# ControlBoard.net
KiCad netlist of a schematic drawn in Altium Designer
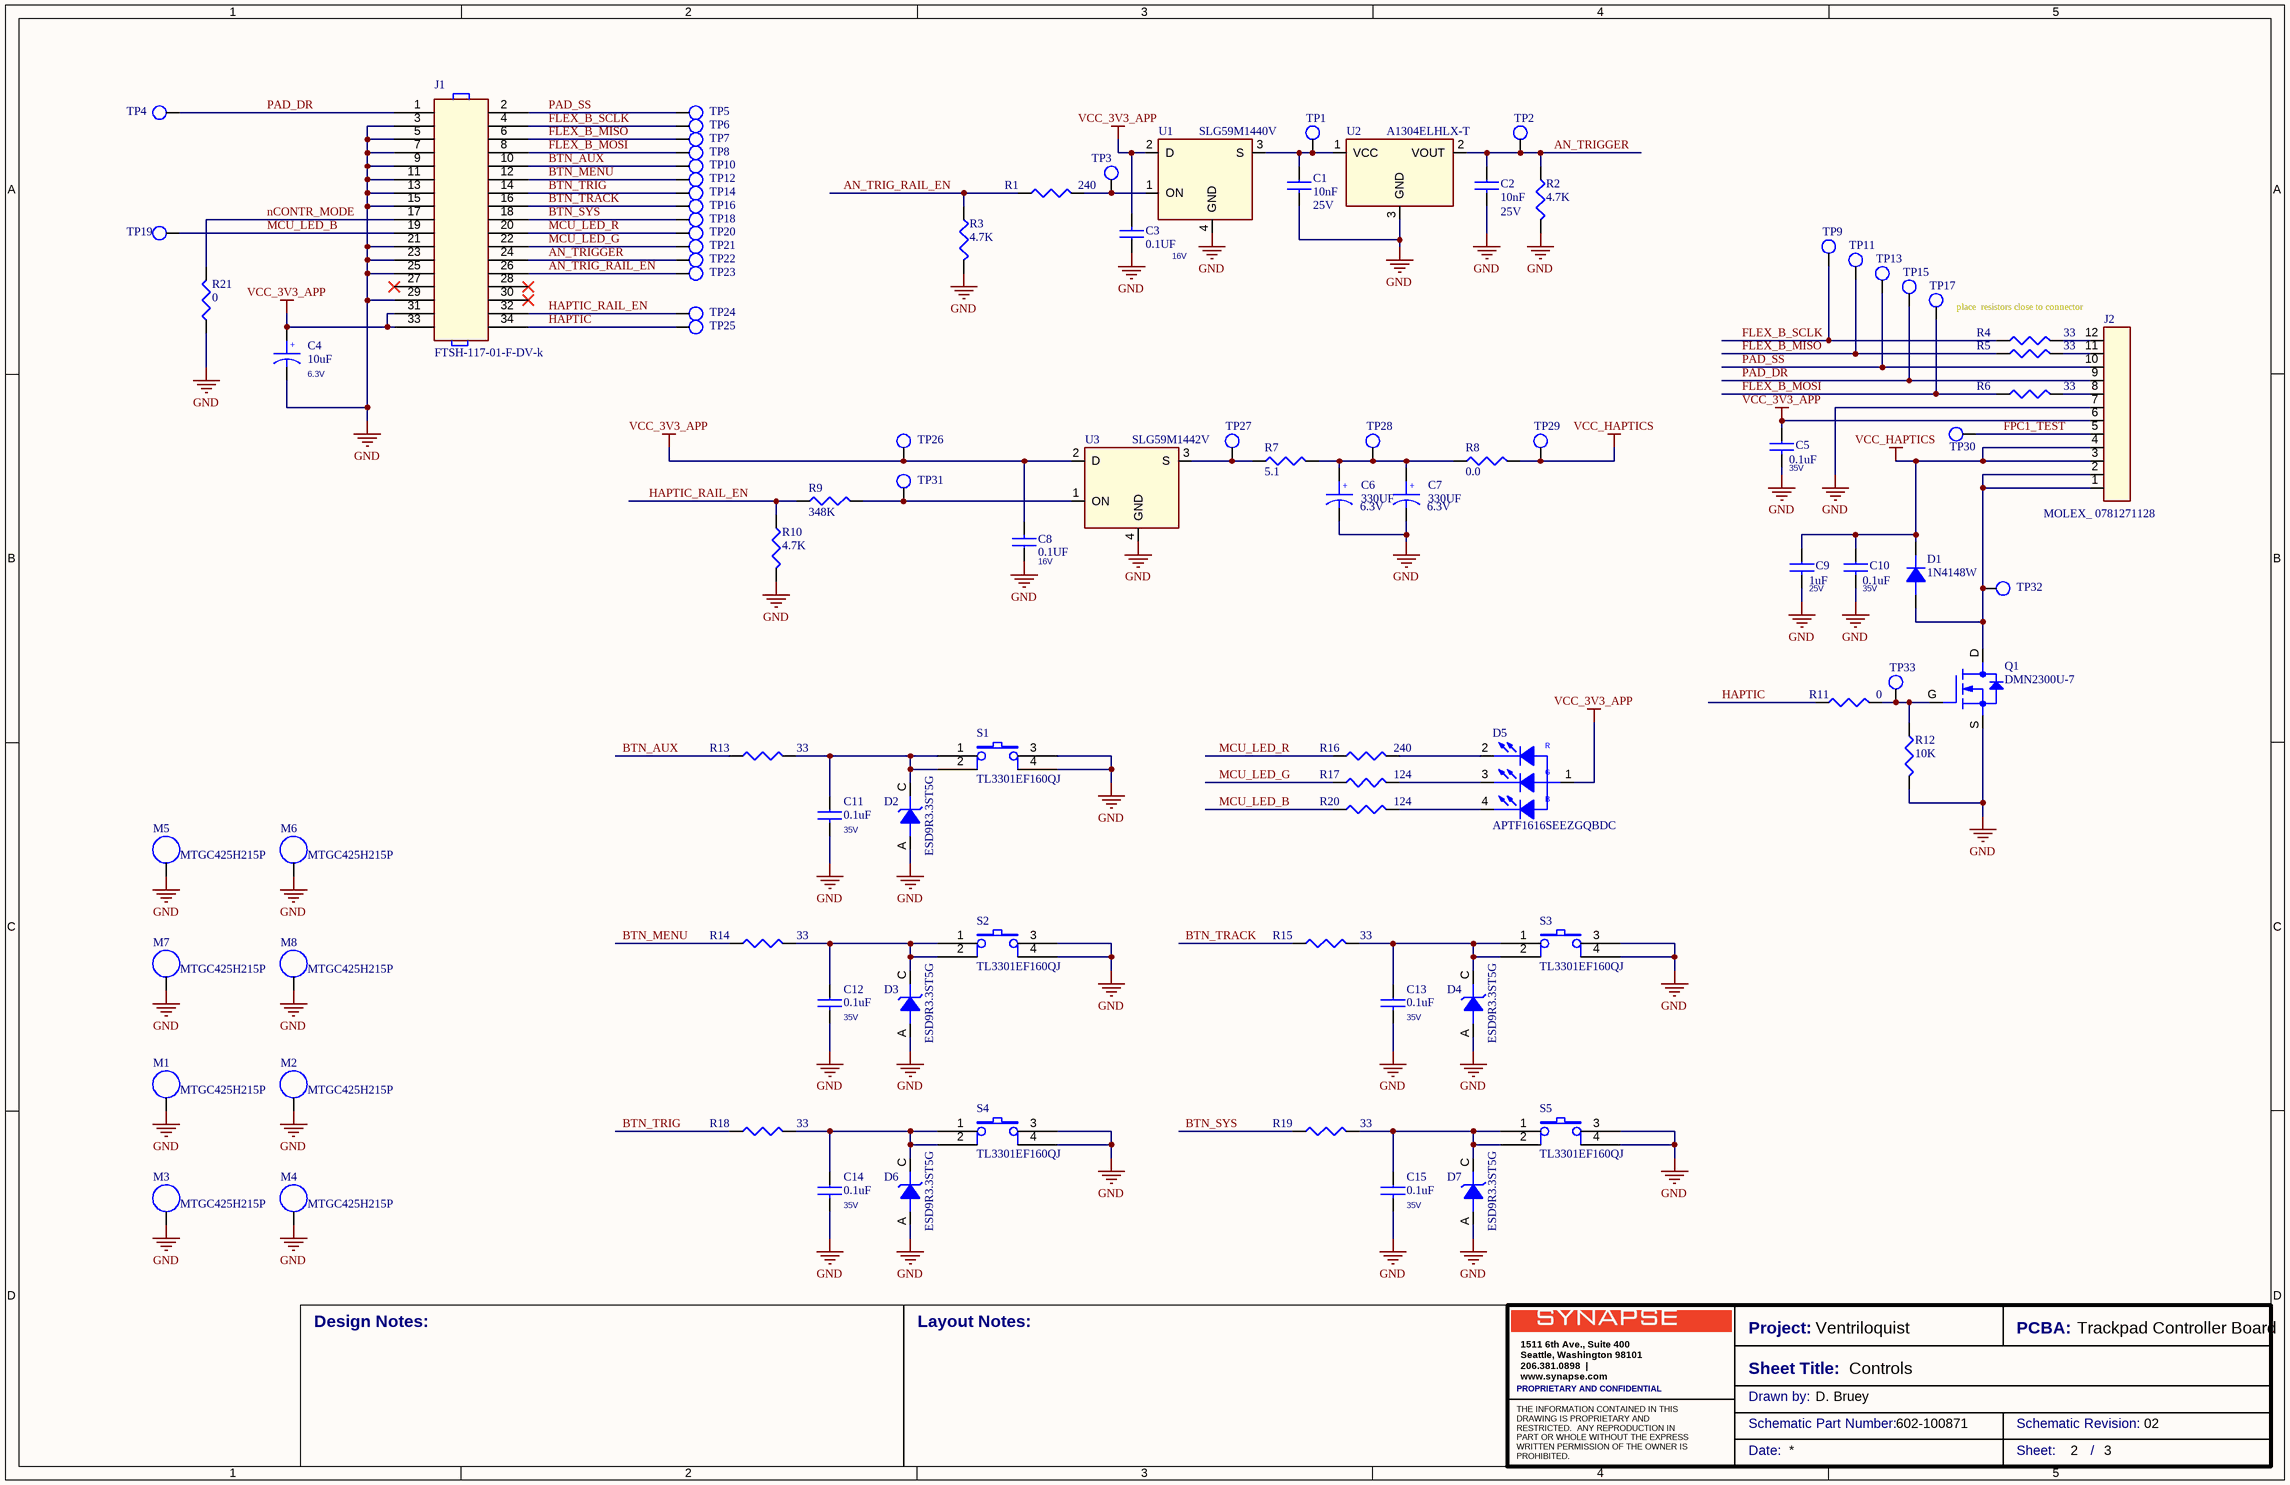
[diagram p0: ControlBoard.SchDoc]

(export (version "E")
  (design (tool "Eeschema 10.0.6"))
  (components
    (comp (ref "C1")
      (value "10nF")
      (footprint "0402-ipcsm_60")
      (description "CAP CER 10000PF 25V 10% X7R 0402")
      (fields (field (name "VOLTAGE") "25V") (field (name "MFG") "TDK") (field (name "TOLERANCE") "10%"))
      (libsource (lib "SynapseLibrary") (part "CAP"))
    )
    (comp (ref "C2")
      (value "10nF")
      (footprint "0402-ipcsm_60")
      (description "CAP CER 10000PF 25V 10% X7R 0402")
      (fields (field (name "VOLTAGE") "25V") (field (name "MFG") "TDK") (field (name "TOLERANCE") "10%"))
      (libsource (lib "SynapseLibrary") (part "CAP"))
    )
    (comp (ref "C3")
      (value "0.1UF")
      (footprint "0603-ipcsm_90")
      (description "CAP CER 0.1UF 16V 5% X7R 0603")
      (fields (field (name "VOLTAGE") "16V") (field (name "MFG") "Kemet") (field (name "TOLERANCE") "5%"))
      (libsource (lib "SynapseLibrary") (part "CAP"))
    )
    (comp (ref "C4")
      (value "10uF")
      (footprint "c-0603-POL_35H")
      (description "CAP TANT 10UF 6.3V 20% 0603")
      (fields
        (field (name "VOLTAGE") "6.3V")
        (field (name "MFG") "Vishay/Sprague")
        (field (name "TOLERANCE") "20%")
      )
      (libsource (lib "SynapseLibrary") (part "CAP_POL"))
    )
    (comp (ref "C5")
      (value "0.1uF")
      (footprint "0402-IPCsm_55")
      (description "CAP CER 0.1UF 35V 10% X5R 0402")
      (fields
        (field (name "VOLTAGE") "35V")
        (field (name "MFG") "TAIYO YUDEN")
        (field (name "TOLERANCE") "±10%")
      )
      (libsource (lib "SynapseLibrary") (part "CAP"))
    )
    (comp (ref "C6")
      (value "330UF")
      (footprint "c-elect_FK-D8")
      (description "CAP ALUM 330UF 20% 6.3V SMD")
      (fields
        (field (name "VOLTAGE") "6.3V")
        (field (name "MFG") "PANASONIC")
        (field (name "TOLERANCE") "20%")
      )
      (libsource (lib "SynapseLibrary") (part "CAP_POL"))
    )
    (comp (ref "C7")
      (value "330UF")
      (footprint "c-elect_FK-D8")
      (description "CAP ALUM 330UF 20% 6.3V SMD")
      (fields
        (field (name "VOLTAGE") "6.3V")
        (field (name "MFG") "PANASONIC")
        (field (name "TOLERANCE") "20%")
      )
      (libsource (lib "SynapseLibrary") (part "CAP_POL"))
    )
    (comp (ref "C8")
      (value "0.1UF")
      (footprint "0603-ipcsm_90")
      (description "CAP CER 0.1UF 16V 5% X7R 0603")
      (fields (field (name "VOLTAGE") "16V") (field (name "MFG") "Kemet") (field (name "TOLERANCE") "5%"))
      (libsource (lib "SynapseLibrary") (part "CAP"))
    )
    (comp (ref "C9")
      (value "1uF")
      (footprint "0603-IPCsm_90")
      (description "CAP CER 1UF 25V 10% X5R 0603")
      (fields (field (name "VOLTAGE") "25V") (field (name "MFG") "Murata") (field (name "TOLERANCE") "10%"))
      (libsource (lib "SynapseLibrary") (part "CAP"))
    )
    (comp (ref "C10")
      (value "0.1uF")
      (footprint "0402-IPCsm_55")
      (description "CAP CER 0.1UF 35V 10% X5R 0402")
      (fields
        (field (name "VOLTAGE") "35V")
        (field (name "MFG") "TAIYO YUDEN")
        (field (name "TOLERANCE") "±10%")
      )
      (libsource (lib "SynapseLibrary") (part "CAP"))
    )
    (comp (ref "C11")
      (value "0.1uF")
      (footprint "0402-IPCsm_55")
      (description "CAP CER 0.1UF 35V 10% X5R 0402")
      (fields
        (field (name "VOLTAGE") "35V")
        (field (name "MFG") "TAIYO YUDEN")
        (field (name "TOLERANCE") "±10%")
      )
      (libsource (lib "SynapseLibrary") (part "CAP"))
    )
    (comp (ref "C12")
      (value "0.1uF")
      (footprint "0402-IPCsm_55")
      (description "CAP CER 0.1UF 35V 10% X5R 0402")
      (fields
        (field (name "VOLTAGE") "35V")
        (field (name "MFG") "TAIYO YUDEN")
        (field (name "TOLERANCE") "±10%")
      )
      (libsource (lib "SynapseLibrary") (part "CAP"))
    )
    (comp (ref "C13")
      (value "0.1uF")
      (footprint "0402-IPCsm_55")
      (description "CAP CER 0.1UF 35V 10% X5R 0402")
      (fields
        (field (name "VOLTAGE") "35V")
        (field (name "MFG") "TAIYO YUDEN")
        (field (name "TOLERANCE") "±10%")
      )
      (libsource (lib "SynapseLibrary") (part "CAP"))
    )
    (comp (ref "C14")
      (value "0.1uF")
      (footprint "0402-IPCsm_55")
      (description "CAP CER 0.1UF 35V 10% X5R 0402")
      (fields
        (field (name "VOLTAGE") "35V")
        (field (name "MFG") "TAIYO YUDEN")
        (field (name "TOLERANCE") "±10%")
      )
      (libsource (lib "SynapseLibrary") (part "CAP"))
    )
    (comp (ref "C15")
      (value "0.1uF")
      (footprint "0402-IPCsm_55")
      (description "CAP CER 0.1UF 35V 10% X5R 0402")
      (fields
        (field (name "VOLTAGE") "35V")
        (field (name "MFG") "TAIYO YUDEN")
        (field (name "TOLERANCE") "±10%")
      )
      (libsource (lib "SynapseLibrary") (part "CAP"))
    )
    (comp (ref "D1")
      (value "1N4148W")
      (footprint "SOD123_135")
      (description "DIODE SWITCH 100V 0.15A SOD123")
      (fields (field (name "MFG") "Micro Commercial Co") (field (name "VOLTAGE") "100V"))
      (libsource (lib "SynapseLibrary") (part "DIODE"))
    )
    (comp (ref "D2")
      (value "ESD9R3.3ST5G")
      (footprint "sod923-40")
      (description "TVS DIODE 3.3VWM 7.8VC SOD923")
      (fields (field (name "MFG") "On Semiconductor") (field (name "VOLTAGE") "3.3V"))
      (libsource (lib "SynapseLibrary") (part "TVS_UNI"))
    )
    (comp (ref "D3")
      (value "ESD9R3.3ST5G")
      (footprint "sod923-40")
      (description "TVS DIODE 3.3VWM 7.8VC SOD923")
      (fields (field (name "MFG") "On Semiconductor") (field (name "VOLTAGE") "3.3V"))
      (libsource (lib "SynapseLibrary") (part "TVS_UNI"))
    )
    (comp (ref "D4")
      (value "ESD9R3.3ST5G")
      (footprint "sod923-40")
      (description "TVS DIODE 3.3VWM 7.8VC SOD923")
      (fields (field (name "MFG") "On Semiconductor") (field (name "VOLTAGE") "3.3V"))
      (libsource (lib "SynapseLibrary") (part "TVS_UNI"))
    )
    (comp (ref "D5")
      (value "APTF1616SEEZGQBDC")
      (footprint "led_RBG_1p6x1p6_sm")
      (description "LED RGB CLEAR 0606 SMD")
      (fields (field (name "MFG") "Kingbright"))
      (libsource (lib "SynapseLibrary") (part "RGB_CA_HT-B3053FCH"))
    )
    (comp (ref "D6")
      (value "ESD9R3.3ST5G")
      (footprint "sod923-40")
      (description "TVS DIODE 3.3VWM 7.8VC SOD923")
      (fields (field (name "MFG") "On Semiconductor") (field (name "VOLTAGE") "3.3V"))
      (libsource (lib "SynapseLibrary") (part "TVS_UNI"))
    )
    (comp (ref "D7")
      (value "ESD9R3.3ST5G")
      (footprint "sod923-40")
      (description "TVS DIODE 3.3VWM 7.8VC SOD923")
      (fields (field (name "MFG") "On Semiconductor") (field (name "VOLTAGE") "3.3V"))
      (libsource (lib "SynapseLibrary") (part "TVS_UNI"))
    )
    (comp (ref "J1")
      (value "FTSH-117-01-F-DV-k")
      (footprint "FTSH-117-01-XXX-DV-K")
      (description "34 Positions Header, Shrouded Connector 0.050\" (1.27mm) Surface Mount Gold")
      (fields (field (name "MFG") "Samtec"))
      (libsource (lib "SynapseLibrary") (part "HEADER 17X2"))
    )
    (comp (ref "J2")
      (value "MOLEX_ 0781271128")
      (footprint "con12_molex_0781271128")
      (description "CONN FFC VERT 12POS 0.50MM SMD")
      (fields (field (name "MFG") "MOLEX"))
      (libsource (lib "SynapseLibrary") (part "HEADER12"))
    )
    (comp (ref "M1")
      (value "MTGC425H215P")
      (footprint "MTGC425H215P")
      (description "MTG, 4.25mm PAD, 2.15mm Plated Hole")
      (libsource (lib "SynapseLibrary") (part "MTG"))
    )
    (comp (ref "M2")
      (value "MTGC425H215P")
      (footprint "MTGC425H215P")
      (description "MTG, 4.25mm PAD, 2.15mm Plated Hole")
      (libsource (lib "SynapseLibrary") (part "MTG"))
    )
    (comp (ref "M3")
      (value "MTGC425H215P")
      (footprint "MTGC425H215P")
      (description "MTG, 4.25mm PAD, 2.15mm Plated Hole")
      (libsource (lib "SynapseLibrary") (part "MTG"))
    )
    (comp (ref "M4")
      (value "MTGC425H215P")
      (footprint "MTGC425H215P")
      (description "MTG, 4.25mm PAD, 2.15mm Plated Hole")
      (libsource (lib "SynapseLibrary") (part "MTG"))
    )
    (comp (ref "M5")
      (value "MTGC425H215P")
      (footprint "MTGC425H215P")
      (description "MTG, 4.25mm PAD, 2.15mm Plated Hole")
      (libsource (lib "SynapseLibrary") (part "MTG"))
    )
    (comp (ref "M6")
      (value "MTGC425H215P")
      (footprint "MTGC425H215P")
      (description "MTG, 4.25mm PAD, 2.15mm Plated Hole")
      (libsource (lib "SynapseLibrary") (part "MTG"))
    )
    (comp (ref "M7")
      (value "MTGC425H215P")
      (footprint "MTGC425H215P")
      (description "MTG, 4.25mm PAD, 2.15mm Plated Hole")
      (libsource (lib "SynapseLibrary") (part "MTG"))
    )
    (comp (ref "M8")
      (value "MTGC425H215P")
      (footprint "MTGC425H215P")
      (description "MTG, 4.25mm PAD, 2.15mm Plated Hole")
      (libsource (lib "SynapseLibrary") (part "MTG"))
    )
    (comp (ref "Q1")
      (value "DMN2300U-7")
      (footprint "SOT23-GSD_47H_DMN2075U")
      (description "MOSFET N-CH 20V 1.24A SOT23")
      (fields (field (name "MFG") "Diodes") (field (name "VOLTAGE") "20V"))
      (libsource (lib "SynapseLibrary") (part "MOSFET_N_EN_3PIN"))
    )
    (comp (ref "R1")
      (value "240")
      (footprint "0402-IPCsm_40")
      (description "RES 240 OHM 1/10W 1% 0402 SMD")
      (fields (field (name "TOLERANCE") "1%") (field (name "MFG") "Panasonic"))
      (libsource (lib "SynapseLibrary") (part "RES"))
    )
    (comp (ref "R2")
      (value "4.7K")
      (footprint "0402-IPCsm_40")
      (description "RES 4.70K OHM 1/10W 1% 0402 SMD")
      (fields (field (name "TOLERANCE") "1.00%") (field (name "VOLTAGE") "50V"))
      (libsource (lib "SynapseLibrary") (part "RES"))
    )
    (comp (ref "R3")
      (value "4.7K")
      (footprint "0402-IPCsm_40")
      (description "RES 4.70K OHM 1/10W 1% 0402 SMD")
      (fields (field (name "TOLERANCE") "1.00%") (field (name "VOLTAGE") "50V"))
      (libsource (lib "SynapseLibrary") (part "RES"))
    )
    (comp (ref "R4")
      (value "33")
      (footprint "0402-IPCsm_40")
      (description "RES 33 OHM 1/16W 5% 0402 SMD")
      (fields (field (name "TOLERANCE") "5.00%") (field (name "VOLTAGE") "50V"))
      (libsource (lib "SynapseLibrary") (part "RES"))
    )
    (comp (ref "R5")
      (value "33")
      (footprint "0402-IPCsm_40")
      (description "RES 33 OHM 1/16W 5% 0402 SMD")
      (fields (field (name "TOLERANCE") "5.00%") (field (name "VOLTAGE") "50V"))
      (libsource (lib "SynapseLibrary") (part "RES"))
    )
    (comp (ref "R6")
      (value "33")
      (footprint "0402-IPCsm_40")
      (description "RES 33 OHM 1/16W 5% 0402 SMD")
      (fields (field (name "TOLERANCE") "5.00%") (field (name "VOLTAGE") "50V"))
      (libsource (lib "SynapseLibrary") (part "RES"))
    )
    (comp (ref "R7")
      (value "5.1")
      (footprint "r-1206_28H")
      (description "RES SMD 5.1 OHM 5% 1/4W 1206")
      (fields (field (name "TOLERANCE") "5.00%") (field (name "MFG") "Yageo"))
      (libsource (lib "SynapseLibrary") (part "RES"))
    )
    (comp (ref "R8")
      (value "0.0")
      (footprint "r-1206_28H")
      (description "RES ZERO OHM 1/4W 5% 1206 SMD")
      (fields (field (name "TOLERANCE") "5.00%") (field (name "VOLTAGE") "200V"))
      (libsource (lib "SynapseLibrary") (part "RES"))
    )
    (comp (ref "R9")
      (value "348K")
      (footprint "0402-IPCsm_40")
      (description "RES SMD 348K OHM 1% 1/10W 0402")
      (fields (field (name "TOLERANCE") "1.00%") (field (name "MFG") "PANASONIC"))
      (libsource (lib "SynapseLibrary") (part "RES"))
    )
    (comp (ref "R10")
      (value "4.7K")
      (footprint "0402-IPCsm_40")
      (description "RES 4.70K OHM 1/10W 1% 0402 SMD")
      (fields (field (name "TOLERANCE") "1.00%") (field (name "VOLTAGE") "50V"))
      (libsource (lib "SynapseLibrary") (part "RES"))
    )
    (comp (ref "R11")
      (value "0")
      (footprint "0402-IPCsm_40")
      (description "RES 0.0 OHM 1/10W JUMP 0402 SMD")
      (fields (field (name "TOLERANCE") "5.00%") (field (name "MFG") "PANASONIC"))
      (libsource (lib "SynapseLibrary") (part "RES"))
    )
    (comp (ref "R12")
      (value "10K")
      (footprint "0402-IPCsm_40")
      (description "RES 10K OHM 1/10W 5% 0402 SMD")
      (fields (field (name "TOLERANCE") "5%") (field (name "MFG") "Panasonic"))
      (libsource (lib "SynapseLibrary") (part "RES"))
    )
    (comp (ref "R13")
      (value "33")
      (footprint "0402-IPCsm_40")
      (description "RES 33 OHM 1/16W 5% 0402 SMD")
      (fields (field (name "TOLERANCE") "5.00%") (field (name "VOLTAGE") "50V"))
      (libsource (lib "SynapseLibrary") (part "RES"))
    )
    (comp (ref "R14")
      (value "33")
      (footprint "0402-IPCsm_40")
      (description "RES 33 OHM 1/16W 5% 0402 SMD")
      (fields (field (name "TOLERANCE") "5.00%") (field (name "VOLTAGE") "50V"))
      (libsource (lib "SynapseLibrary") (part "RES"))
    )
    (comp (ref "R15")
      (value "33")
      (footprint "0402-IPCsm_40")
      (description "RES 33 OHM 1/16W 5% 0402 SMD")
      (fields (field (name "TOLERANCE") "5.00%") (field (name "VOLTAGE") "50V"))
      (libsource (lib "SynapseLibrary") (part "RES"))
    )
    (comp (ref "R16")
      (value "240")
      (footprint "0402-IPCsm_40")
      (description "RES 240 OHM 1/10W 1% 0402 SMD")
      (fields (field (name "TOLERANCE") "1%") (field (name "MFG") "Panasonic"))
      (libsource (lib "SynapseLibrary") (part "RES"))
    )
    (comp (ref "R17")
      (value "124")
      (footprint "0402-IPCsm_40")
      (description "RES SMD 124 OHM 1% 1/16W 0402")
      (fields (field (name "TOLERANCE") "1.00%") (field (name "MFG") "Yageo"))
      (libsource (lib "SynapseLibrary") (part "RES"))
    )
    (comp (ref "R18")
      (value "33")
      (footprint "0402-IPCsm_40")
      (description "RES 33 OHM 1/16W 5% 0402 SMD")
      (fields (field (name "TOLERANCE") "5.00%") (field (name "VOLTAGE") "50V"))
      (libsource (lib "SynapseLibrary") (part "RES"))
    )
    (comp (ref "R19")
      (value "33")
      (footprint "0402-IPCsm_40")
      (description "RES 33 OHM 1/16W 5% 0402 SMD")
      (fields (field (name "TOLERANCE") "5.00%") (field (name "VOLTAGE") "50V"))
      (libsource (lib "SynapseLibrary") (part "RES"))
    )
    (comp (ref "R20")
      (value "124")
      (footprint "0402-IPCsm_40")
      (description "RES SMD 124 OHM 1% 1/16W 0402")
      (fields (field (name "TOLERANCE") "1.00%") (field (name "MFG") "Yageo"))
      (libsource (lib "SynapseLibrary") (part "RES"))
    )
    (comp (ref "R21")
      (value "0")
      (footprint "0402-IPCsm_40")
      (description "RES 0.0 OHM 1/10W JUMP 0402 SMD")
      (fields (field (name "TOLERANCE") "5.00%") (field (name "MFG") "PANASONIC"))
      (libsource (lib "SynapseLibrary") (part "RES"))
    )
    (comp (ref "S1")
      (value "TL3301EF160QJ")
      (footprint "SW_TL3301_J")
      (description "SWITCH TACTILE SPST-NO 0.05A 12V")
      (fields (field (name "PART NUMBER") "TL3301AF260QG") (field (name "MANUFACTURER") "E-Switch"))
      (libsource (lib "SynapseLibrary") (part "ESWITCH_TL3301AF"))
    )
    (comp (ref "S2")
      (value "TL3301EF160QJ")
      (footprint "SW_TL3301_J")
      (description "SWITCH TACTILE SPST-NO 0.05A 12V")
      (fields (field (name "PART NUMBER") "TL3301AF260QG") (field (name "MANUFACTURER") "E-Switch"))
      (libsource (lib "SynapseLibrary") (part "ESWITCH_TL3301AF"))
    )
    (comp (ref "S3")
      (value "TL3301EF160QJ")
      (footprint "SW_TL3301_J")
      (description "SWITCH TACTILE SPST-NO 0.05A 12V")
      (fields (field (name "PART NUMBER") "TL3301AF260QG") (field (name "MANUFACTURER") "E-Switch"))
      (libsource (lib "SynapseLibrary") (part "ESWITCH_TL3301AF"))
    )
    (comp (ref "S4")
      (value "TL3301EF160QJ")
      (footprint "SW_TL3301_J")
      (description "SWITCH TACTILE SPST-NO 0.05A 12V")
      (fields (field (name "PART NUMBER") "TL3301AF260QG") (field (name "MANUFACTURER") "E-Switch"))
      (libsource (lib "SynapseLibrary") (part "ESWITCH_TL3301AF"))
    )
    (comp (ref "S5")
      (value "TL3301EF160QJ")
      (footprint "SW_TL3301_J")
      (description "SWITCH TACTILE SPST-NO 0.05A 12V")
      (fields (field (name "PART NUMBER") "TL3301AF260QG") (field (name "MANUFACTURER") "E-Switch"))
      (libsource (lib "SynapseLibrary") (part "ESWITCH_TL3301AF"))
    )
    (comp (ref "TP1")
      (value "tp-1mm")
      (footprint "TP-S100_SMT")
      (description "TESTPOINT, 1MM SMD, Square pad, Round SM opening")
      (fields (field (name "MFG") "NA"))
      (libsource (lib "SynapseLibrary") (part "tp_smt"))
    )
    (comp (ref "TP2")
      (value "tp-1mm")
      (footprint "TP-S100_SMT")
      (description "TESTPOINT, 1MM SMD, Square pad, Round SM opening")
      (fields (field (name "MFG") "NA"))
      (libsource (lib "SynapseLibrary") (part "tp_smt"))
    )
    (comp (ref "TP3")
      (value "tp-1mm")
      (footprint "TP-S100_SMT")
      (description "TESTPOINT, 1MM SMD, Square pad, Round SM opening")
      (fields (field (name "MFG") "NA"))
      (libsource (lib "SynapseLibrary") (part "tp_smt"))
    )
    (comp (ref "TP4")
      (value "tp-1mm")
      (footprint "TP-S100_SMT")
      (description "TESTPOINT, 1MM SMD, Square pad, Round SM opening")
      (fields (field (name "MFG") "NA"))
      (libsource (lib "SynapseLibrary") (part "tp_smt"))
    )
    (comp (ref "TP5")
      (value "tp-1mm")
      (footprint "TP-S100_SMT")
      (description "TESTPOINT, 1MM SMD, Square pad, Round SM opening")
      (fields (field (name "MFG") "NA"))
      (libsource (lib "SynapseLibrary") (part "tp_smt"))
    )
    (comp (ref "TP6")
      (value "tp-1mm")
      (footprint "TP-S100_SMT")
      (description "TESTPOINT, 1MM SMD, Square pad, Round SM opening")
      (fields (field (name "MFG") "NA"))
      (libsource (lib "SynapseLibrary") (part "tp_smt"))
    )
    (comp (ref "TP7")
      (value "tp-1mm")
      (footprint "TP-S100_SMT")
      (description "TESTPOINT, 1MM SMD, Square pad, Round SM opening")
      (fields (field (name "MFG") "NA"))
      (libsource (lib "SynapseLibrary") (part "tp_smt"))
    )
    (comp (ref "TP8")
      (value "tp-1mm")
      (footprint "TP-S100_SMT")
      (description "TESTPOINT, 1MM SMD, Square pad, Round SM opening")
      (fields (field (name "MFG") "NA"))
      (libsource (lib "SynapseLibrary") (part "tp_smt"))
    )
    (comp (ref "TP9")
      (value "tp-1mm")
      (footprint "TP-S100_SMT")
      (description "TESTPOINT, 1MM SMD, Square pad, Round SM opening")
      (fields (field (name "MFG") "NA"))
      (libsource (lib "SynapseLibrary") (part "tp_smt"))
    )
    (comp (ref "TP10")
      (value "tp-1mm")
      (footprint "TP-S100_SMT")
      (description "TESTPOINT, 1MM SMD, Square pad, Round SM opening")
      (fields (field (name "MFG") "NA"))
      (libsource (lib "SynapseLibrary") (part "tp_smt"))
    )
    (comp (ref "TP11")
      (value "tp-1mm")
      (footprint "TP-S100_SMT")
      (description "TESTPOINT, 1MM SMD, Square pad, Round SM opening")
      (fields (field (name "MFG") "NA"))
      (libsource (lib "SynapseLibrary") (part "tp_smt"))
    )
    (comp (ref "TP12")
      (value "tp-1mm")
      (footprint "TP-S100_SMT")
      (description "TESTPOINT, 1MM SMD, Square pad, Round SM opening")
      (fields (field (name "MFG") "NA"))
      (libsource (lib "SynapseLibrary") (part "tp_smt"))
    )
    (comp (ref "TP13")
      (value "tp-1mm")
      (footprint "TP-S100_SMT")
      (description "TESTPOINT, 1MM SMD, Square pad, Round SM opening")
      (fields (field (name "MFG") "NA"))
      (libsource (lib "SynapseLibrary") (part "tp_smt"))
    )
    (comp (ref "TP14")
      (value "tp-1mm")
      (footprint "TP-S100_SMT")
      (description "TESTPOINT, 1MM SMD, Square pad, Round SM opening")
      (fields (field (name "MFG") "NA"))
      (libsource (lib "SynapseLibrary") (part "tp_smt"))
    )
    (comp (ref "TP15")
      (value "tp-1mm")
      (footprint "TP-S100_SMT")
      (description "TESTPOINT, 1MM SMD, Square pad, Round SM opening")
      (fields (field (name "MFG") "NA"))
      (libsource (lib "SynapseLibrary") (part "tp_smt"))
    )
    (comp (ref "TP16")
      (value "tp-1mm")
      (footprint "TP-S100_SMT")
      (description "TESTPOINT, 1MM SMD, Square pad, Round SM opening")
      (fields (field (name "MFG") "NA"))
      (libsource (lib "SynapseLibrary") (part "tp_smt"))
    )
    (comp (ref "TP17")
      (value "tp-1mm")
      (footprint "TP-S100_SMT")
      (description "TESTPOINT, 1MM SMD, Square pad, Round SM opening")
      (fields (field (name "MFG") "NA"))
      (libsource (lib "SynapseLibrary") (part "tp_smt"))
    )
    (comp (ref "TP18")
      (value "tp-1mm")
      (footprint "TP-S100_SMT")
      (description "TESTPOINT, 1MM SMD, Square pad, Round SM opening")
      (fields (field (name "MFG") "NA"))
      (libsource (lib "SynapseLibrary") (part "tp_smt"))
    )
    (comp (ref "TP19")
      (value "tp-1mm")
      (footprint "TP-S100_SMT")
      (description "TESTPOINT, 1MM SMD, Square pad, Round SM opening")
      (fields (field (name "MFG") "NA"))
      (libsource (lib "SynapseLibrary") (part "tp_smt"))
    )
    (comp (ref "TP20")
      (value "tp-1mm")
      (footprint "TP-S100_SMT")
      (description "TESTPOINT, 1MM SMD, Square pad, Round SM opening")
      (fields (field (name "MFG") "NA"))
      (libsource (lib "SynapseLibrary") (part "tp_smt"))
    )
    (comp (ref "TP21")
      (value "tp-1mm")
      (footprint "TP-S100_SMT")
      (description "TESTPOINT, 1MM SMD, Square pad, Round SM opening")
      (fields (field (name "MFG") "NA"))
      (libsource (lib "SynapseLibrary") (part "tp_smt"))
    )
    (comp (ref "TP22")
      (value "tp-1mm")
      (footprint "TP-S100_SMT")
      (description "TESTPOINT, 1MM SMD, Square pad, Round SM opening")
      (fields (field (name "MFG") "NA"))
      (libsource (lib "SynapseLibrary") (part "tp_smt"))
    )
    (comp (ref "TP23")
      (value "tp-1mm")
      (footprint "TP-S100_SMT")
      (description "TESTPOINT, 1MM SMD, Square pad, Round SM opening")
      (fields (field (name "MFG") "NA"))
      (libsource (lib "SynapseLibrary") (part "tp_smt"))
    )
    (comp (ref "TP24")
      (value "tp-1mm")
      (footprint "TP-S100_SMT")
      (description "TESTPOINT, 1MM SMD, Square pad, Round SM opening")
      (fields (field (name "MFG") "NA"))
      (libsource (lib "SynapseLibrary") (part "tp_smt"))
    )
    (comp (ref "TP25")
      (value "tp-1mm")
      (footprint "TP-S100_SMT")
      (description "TESTPOINT, 1MM SMD, Square pad, Round SM opening")
      (fields (field (name "MFG") "NA"))
      (libsource (lib "SynapseLibrary") (part "tp_smt"))
    )
    (comp (ref "TP26")
      (value "tp-1mm")
      (footprint "TP-S100_SMT")
      (description "TESTPOINT, 1MM SMD, Square pad, Round SM opening")
      (fields (field (name "MFG") "NA"))
      (libsource (lib "SynapseLibrary") (part "tp_smt"))
    )
    (comp (ref "TP27")
      (value "tp-1mm")
      (footprint "TP-S100_SMT")
      (description "TESTPOINT, 1MM SMD, Square pad, Round SM opening")
      (fields (field (name "MFG") "NA"))
      (libsource (lib "SynapseLibrary") (part "tp_smt"))
    )
    (comp (ref "TP28")
      (value "tp-1mm")
      (footprint "TP-S100_SMT")
      (description "TESTPOINT, 1MM SMD, Square pad, Round SM opening")
      (fields (field (name "MFG") "NA"))
      (libsource (lib "SynapseLibrary") (part "tp_smt"))
    )
    (comp (ref "TP29")
      (value "tp-1mm")
      (footprint "TP-S100_SMT")
      (description "TESTPOINT, 1MM SMD, Square pad, Round SM opening")
      (fields (field (name "MFG") "NA"))
      (libsource (lib "SynapseLibrary") (part "tp_smt"))
    )
    (comp (ref "TP30")
      (value "tp-1mm")
      (footprint "TP-S100_SMT")
      (description "TESTPOINT, 1MM SMD, Square pad, Round SM opening")
      (fields (field (name "MFG") "NA"))
      (libsource (lib "SynapseLibrary") (part "tp_smt"))
    )
    (comp (ref "TP31")
      (value "tp-1mm")
      (footprint "TP-S100_SMT")
      (description "TESTPOINT, 1MM SMD, Square pad, Round SM opening")
      (fields (field (name "MFG") "NA"))
      (libsource (lib "SynapseLibrary") (part "tp_smt"))
    )
    (comp (ref "TP32")
      (value "tp-1mm")
      (footprint "TP-S100_SMT")
      (description "TESTPOINT, 1MM SMD, Square pad, Round SM opening")
      (fields (field (name "MFG") "NA"))
      (libsource (lib "SynapseLibrary") (part "tp_smt"))
    )
    (comp (ref "TP33")
      (value "tp-1mm")
      (footprint "TP-S100_SMT")
      (description "TESTPOINT, 1MM SMD, Square pad, Round SM opening")
      (fields (field (name "MFG") "NA"))
      (libsource (lib "SynapseLibrary") (part "tp_smt"))
    )
    (comp (ref "U1")
      (value "SLG59M1440V")
      (footprint "STDFN4_SLG59M144x")
      (description "Single 40mohm 1A Load Switch w/discharge")
      (fields (field (name "MFG") "Silego") (field (name "VOLTAGE") "2.5-5.5V"))
      (libsource (lib "SynapseLibrary") (part "SLG59M144xV"))
    )
    (comp (ref "U2")
      (value "A1304ELHLX-T")
      (footprint "sot23-3_A1304_113")
      (description "IC HALL EFFECT SENSOR SOT-23W")
      (fields (field (name "MFG") "Allegro MicroSystems, LLC") (field (name "VOLTAGE") "3V ~ 3.6V"))
      (libsource (lib "SynapseLibrary") (part "A1304ELHLX-T"))
    )
    (comp (ref "U3")
      (value "SLG59M1442V")
      (footprint "STDFN4_SLG59M144x")
      (description "Single 40mohm 1A Load Switch")
      (fields (field (name "MFG") "Silego") (field (name "VOLTAGE") "2.5-5.5V"))
      (libsource (lib "SynapseLibrary") (part "SLG59M144xV"))
    )
  )
  (nets
    (net (code "1") (name "/AN_TRIGGER") (class "Default")
      (node (ref "C2") (pin "1") (pinfunction "1_1") (pintype "passive"))
      (node (ref "J1") (pin "24") (pinfunction "24_24") (pintype "passive"))
      (node (ref "R2") (pin "1") (pinfunction "1_1") (pintype "passive"))
      (node (ref "TP2") (pin "1") (pinfunction "TP_1") (pintype "passive"))
      (node (ref "TP22") (pin "1") (pinfunction "TP_1") (pintype "passive"))
      (node (ref "U2") (pin "2") (pinfunction "VOUT_2") (pintype "passive"))
    )
    (net (code "2") (name "/AN_TRIG_RAIL_EN") (class "Default")
      (node (ref "J1") (pin "26") (pinfunction "26_26") (pintype "passive"))
      (node (ref "R1") (pin "1") (pinfunction "1_1") (pintype "passive"))
      (node (ref "R3") (pin "1") (pinfunction "1_1") (pintype "passive"))
      (node (ref "TP23") (pin "1") (pinfunction "TP_1") (pintype "passive"))
    )
    (net (code "3") (name "/BTN_AUX") (class "Default")
      (node (ref "J1") (pin "10") (pinfunction "10_10") (pintype "passive"))
      (node (ref "R13") (pin "1") (pinfunction "1_1") (pintype "passive"))
      (node (ref "TP10") (pin "1") (pinfunction "TP_1") (pintype "passive"))
    )
    (net (code "4") (name "/BTN_MENU") (class "Default")
      (node (ref "J1") (pin "12") (pinfunction "12_12") (pintype "passive"))
      (node (ref "R14") (pin "1") (pinfunction "1_1") (pintype "passive"))
      (node (ref "TP12") (pin "1") (pinfunction "TP_1") (pintype "passive"))
    )
    (net (code "5") (name "/BTN_SYS") (class "Default")
      (node (ref "J1") (pin "18") (pinfunction "18_18") (pintype "passive"))
      (node (ref "R19") (pin "1") (pinfunction "1_1") (pintype "passive"))
      (node (ref "TP18") (pin "1") (pinfunction "TP_1") (pintype "passive"))
    )
    (net (code "6") (name "/BTN_TRACK") (class "Default")
      (node (ref "J1") (pin "16") (pinfunction "16_16") (pintype "passive"))
      (node (ref "R15") (pin "1") (pinfunction "1_1") (pintype "passive"))
      (node (ref "TP16") (pin "1") (pinfunction "TP_1") (pintype "passive"))
    )
    (net (code "7") (name "/BTN_TRIG") (class "Default")
      (node (ref "J1") (pin "14") (pinfunction "14_14") (pintype "passive"))
      (node (ref "R18") (pin "1") (pinfunction "1_1") (pintype "passive"))
      (node (ref "TP14") (pin "1") (pinfunction "TP_1") (pintype "passive"))
    )
    (net (code "8") (name "/FLEX_B_MISO") (class "Default")
      (node (ref "J1") (pin "6") (pinfunction "6_6") (pintype "passive"))
      (node (ref "R5") (pin "1") (pinfunction "1_1") (pintype "passive"))
      (node (ref "TP11") (pin "1") (pinfunction "TP_1") (pintype "passive"))
      (node (ref "TP7") (pin "1") (pinfunction "TP_1") (pintype "passive"))
    )
    (net (code "9") (name "/FLEX_B_MOSI") (class "Default")
      (node (ref "J1") (pin "8") (pinfunction "8_8") (pintype "passive"))
      (node (ref "R6") (pin "1") (pinfunction "1_1") (pintype "passive"))
      (node (ref "TP17") (pin "1") (pinfunction "TP_1") (pintype "passive"))
      (node (ref "TP8") (pin "1") (pinfunction "TP_1") (pintype "passive"))
    )
    (net (code "10") (name "/FLEX_B_SCLK") (class "Default")
      (node (ref "J1") (pin "4") (pinfunction "4_4") (pintype "passive"))
      (node (ref "R4") (pin "1") (pinfunction "1_1") (pintype "passive"))
      (node (ref "TP6") (pin "1") (pinfunction "TP_1") (pintype "passive"))
      (node (ref "TP9") (pin "1") (pinfunction "TP_1") (pintype "passive"))
    )
    (net (code "11") (name "/FPC1_TEST") (class "Default")
      (node (ref "J2") (pin "5") (pinfunction "5_5") (pintype "passive"))
      (node (ref "TP30") (pin "1") (pinfunction "TP_1") (pintype "passive"))
    )
    (net (code "12") (name "/HAPTIC") (class "Default")
      (node (ref "J1") (pin "34") (pinfunction "34_34") (pintype "passive"))
      (node (ref "R11") (pin "1") (pinfunction "1_1") (pintype "passive"))
      (node (ref "TP25") (pin "1") (pinfunction "TP_1") (pintype "passive"))
    )
    (net (code "13") (name "/HAPTIC_RAIL_EN") (class "Default")
      (node (ref "J1") (pin "32") (pinfunction "32_32") (pintype "passive"))
      (node (ref "R10") (pin "1") (pinfunction "1_1") (pintype "passive"))
      (node (ref "R9") (pin "1") (pinfunction "1_1") (pintype "passive"))
      (node (ref "TP24") (pin "1") (pinfunction "TP_1") (pintype "passive"))
    )
    (net (code "14") (name "/MCU_LED_B") (class "Default")
      (node (ref "J1") (pin "19") (pinfunction "19_19") (pintype "passive"))
      (node (ref "R20") (pin "1") (pinfunction "1_1") (pintype "passive"))
      (node (ref "TP19") (pin "1") (pinfunction "TP_1") (pintype "passive"))
    )
    (net (code "15") (name "/MCU_LED_G") (class "Default")
      (node (ref "J1") (pin "22") (pinfunction "22_22") (pintype "passive"))
      (node (ref "R17") (pin "1") (pinfunction "1_1") (pintype "passive"))
      (node (ref "TP21") (pin "1") (pinfunction "TP_1") (pintype "passive"))
    )
    (net (code "16") (name "/MCU_LED_R") (class "Default")
      (node (ref "J1") (pin "20") (pinfunction "20_20") (pintype "passive"))
      (node (ref "R16") (pin "1") (pinfunction "1_1") (pintype "passive"))
      (node (ref "TP20") (pin "1") (pinfunction "TP_1") (pintype "passive"))
    )
    (net (code "17") (name "/PAD_DR") (class "Default")
      (node (ref "J1") (pin "1") (pinfunction "1_1") (pintype "passive"))
      (node (ref "J2") (pin "9") (pinfunction "9_9") (pintype "passive"))
      (node (ref "TP15") (pin "1") (pinfunction "TP_1") (pintype "passive"))
      (node (ref "TP4") (pin "1") (pinfunction "TP_1") (pintype "passive"))
    )
    (net (code "18") (name "/PAD_SS") (class "Default")
      (node (ref "J1") (pin "2") (pinfunction "2_2") (pintype "passive"))
      (node (ref "J2") (pin "10") (pinfunction "10_10") (pintype "passive"))
      (node (ref "TP13") (pin "1") (pinfunction "TP_1") (pintype "passive"))
      (node (ref "TP5") (pin "1") (pinfunction "TP_1") (pintype "passive"))
    )
    (net (code "19") (name "/nCONTR_MODE") (class "Default")
      (node (ref "J1") (pin "17") (pinfunction "17_17") (pintype "passive"))
      (node (ref "R21") (pin "2") (pinfunction "2_2") (pintype "passive"))
    )
    (net (code "20") (name "GND") (class "Default")
      (node (ref "C1") (pin "2") (pinfunction "2_2") (pintype "passive"))
      (node (ref "C10") (pin "2") (pinfunction "2_2") (pintype "passive"))
      (node (ref "C11") (pin "2") (pinfunction "2_2") (pintype "passive"))
      (node (ref "C12") (pin "2") (pinfunction "2_2") (pintype "passive"))
      (node (ref "C13") (pin "2") (pinfunction "2_2") (pintype "passive"))
      (node (ref "C14") (pin "2") (pinfunction "2_2") (pintype "passive"))
      (node (ref "C15") (pin "2") (pinfunction "2_2") (pintype "passive"))
      (node (ref "C2") (pin "2") (pinfunction "2_2") (pintype "passive"))
      (node (ref "C3") (pin "1") (pinfunction "1_1") (pintype "passive"))
      (node (ref "C4") (pin "N") (pinfunction "NEG_N") (pintype "passive"))
      (node (ref "C5") (pin "2") (pinfunction "2_2") (pintype "passive"))
      (node (ref "C6") (pin "N") (pinfunction "NEG_N") (pintype "passive"))
      (node (ref "C7") (pin "N") (pinfunction "NEG_N") (pintype "passive"))
      (node (ref "C8") (pin "1") (pinfunction "1_1") (pintype "passive"))
      (node (ref "C9") (pin "2") (pinfunction "2_2") (pintype "passive"))
      (node (ref "D2") (pin "A") (pinfunction "A_A") (pintype "passive"))
      (node (ref "D3") (pin "A") (pinfunction "A_A") (pintype "passive"))
      (node (ref "D4") (pin "A") (pinfunction "A_A") (pintype "passive"))
      (node (ref "D6") (pin "A") (pinfunction "A_A") (pintype "passive"))
      (node (ref "D7") (pin "A") (pinfunction "A_A") (pintype "passive"))
      (node (ref "J1") (pin "11") (pinfunction "11_11") (pintype "passive"))
      (node (ref "J1") (pin "13") (pinfunction "13_13") (pintype "passive"))
      (node (ref "J1") (pin "15") (pinfunction "15_15") (pintype "passive"))
      (node (ref "J1") (pin "21") (pinfunction "21_21") (pintype "passive"))
      (node (ref "J1") (pin "23") (pinfunction "23_23") (pintype "passive"))
      (node (ref "J1") (pin "25") (pinfunction "25_25") (pintype "passive"))
      (node (ref "J1") (pin "29") (pinfunction "29_29") (pintype "passive"))
      (node (ref "J1") (pin "3") (pinfunction "3_3") (pintype "passive"))
      (node (ref "J1") (pin "5") (pinfunction "5_5") (pintype "passive"))
      (node (ref "J1") (pin "7") (pinfunction "7_7") (pintype "passive"))
      (node (ref "J1") (pin "9") (pinfunction "9_9") (pintype "passive"))
      (node (ref "J2") (pin "7") (pinfunction "7_7") (pintype "passive"))
      (node (ref "M1") (pin "1") (pinfunction "1_1") (pintype "passive"))
      (node (ref "M2") (pin "1") (pinfunction "1_1") (pintype "passive"))
      (node (ref "M3") (pin "1") (pinfunction "1_1") (pintype "passive"))
      (node (ref "M4") (pin "1") (pinfunction "1_1") (pintype "passive"))
      (node (ref "M5") (pin "1") (pinfunction "1_1") (pintype "passive"))
      (node (ref "M6") (pin "1") (pinfunction "1_1") (pintype "passive"))
      (node (ref "M7") (pin "1") (pinfunction "1_1") (pintype "passive"))
      (node (ref "M8") (pin "1") (pinfunction "1_1") (pintype "passive"))
      (node (ref "Q1") (pin "S") (pinfunction "S_S") (pintype "passive"))
      (node (ref "R10") (pin "2") (pinfunction "2_2") (pintype "passive"))
      (node (ref "R12") (pin "2") (pinfunction "2_2") (pintype "passive"))
      (node (ref "R2") (pin "2") (pinfunction "2_2") (pintype "passive"))
      (node (ref "R21") (pin "1") (pinfunction "1_1") (pintype "passive"))
      (node (ref "R3") (pin "2") (pinfunction "2_2") (pintype "passive"))
      (node (ref "S1") (pin "3") (pinfunction "3_3") (pintype "passive"))
      (node (ref "S1") (pin "4") (pinfunction "4_4") (pintype "passive"))
      (node (ref "S2") (pin "3") (pinfunction "3_3") (pintype "passive"))
      (node (ref "S2") (pin "4") (pinfunction "4_4") (pintype "passive"))
      (node (ref "S3") (pin "3") (pinfunction "3_3") (pintype "passive"))
      (node (ref "S3") (pin "4") (pinfunction "4_4") (pintype "passive"))
      (node (ref "S4") (pin "3") (pinfunction "3_3") (pintype "passive"))
      (node (ref "S4") (pin "4") (pinfunction "4_4") (pintype "passive"))
      (node (ref "S5") (pin "3") (pinfunction "3_3") (pintype "passive"))
      (node (ref "S5") (pin "4") (pinfunction "4_4") (pintype "passive"))
      (node (ref "U1") (pin "4") (pinfunction "GND_4") (pintype "passive"))
      (node (ref "U2") (pin "3") (pinfunction "GND_3") (pintype "passive"))
      (node (ref "U3") (pin "4") (pinfunction "GND_4") (pintype "passive"))
    )
    (net (code "21") (name "Net-(C6-POS)") (class "Default")
      (node (ref "C6") (pin "P") (pinfunction "POS_P") (pintype "passive"))
      (node (ref "C7") (pin "P") (pinfunction "POS_P") (pintype "passive"))
      (node (ref "R7") (pin "2") (pinfunction "2_2") (pintype "passive"))
      (node (ref "R8") (pin "1") (pinfunction "1_1") (pintype "passive"))
      (node (ref "TP28") (pin "1") (pinfunction "TP_1") (pintype "passive"))
    )
    (net (code "22") (name "Net-(C11-Pad1)") (class "Default")
      (node (ref "C11") (pin "1") (pinfunction "1_1") (pintype "passive"))
      (node (ref "D2") (pin "C") (pinfunction "C_C") (pintype "passive"))
      (node (ref "R13") (pin "2") (pinfunction "2_2") (pintype "passive"))
      (node (ref "S1") (pin "1") (pinfunction "1_1") (pintype "passive"))
      (node (ref "S1") (pin "2") (pinfunction "2_2") (pintype "passive"))
    )
    (net (code "23") (name "Net-(C12-Pad1)") (class "Default")
      (node (ref "C12") (pin "1") (pinfunction "1_1") (pintype "passive"))
      (node (ref "D3") (pin "C") (pinfunction "C_C") (pintype "passive"))
      (node (ref "R14") (pin "2") (pinfunction "2_2") (pintype "passive"))
      (node (ref "S2") (pin "1") (pinfunction "1_1") (pintype "passive"))
      (node (ref "S2") (pin "2") (pinfunction "2_2") (pintype "passive"))
    )
    (net (code "24") (name "Net-(C13-Pad1)") (class "Default")
      (node (ref "C13") (pin "1") (pinfunction "1_1") (pintype "passive"))
      (node (ref "D4") (pin "C") (pinfunction "C_C") (pintype "passive"))
      (node (ref "R15") (pin "2") (pinfunction "2_2") (pintype "passive"))
      (node (ref "S3") (pin "1") (pinfunction "1_1") (pintype "passive"))
      (node (ref "S3") (pin "2") (pinfunction "2_2") (pintype "passive"))
    )
    (net (code "25") (name "Net-(C14-Pad1)") (class "Default")
      (node (ref "C14") (pin "1") (pinfunction "1_1") (pintype "passive"))
      (node (ref "D6") (pin "C") (pinfunction "C_C") (pintype "passive"))
      (node (ref "R18") (pin "2") (pinfunction "2_2") (pintype "passive"))
      (node (ref "S4") (pin "1") (pinfunction "1_1") (pintype "passive"))
      (node (ref "S4") (pin "2") (pinfunction "2_2") (pintype "passive"))
    )
    (net (code "26") (name "Net-(C15-Pad1)") (class "Default")
      (node (ref "C15") (pin "1") (pinfunction "1_1") (pintype "passive"))
      (node (ref "D7") (pin "C") (pinfunction "C_C") (pintype "passive"))
      (node (ref "R19") (pin "2") (pinfunction "2_2") (pintype "passive"))
      (node (ref "S5") (pin "1") (pinfunction "1_1") (pintype "passive"))
      (node (ref "S5") (pin "2") (pinfunction "2_2") (pintype "passive"))
    )
    (net (code "27") (name "Net-(D5-B)") (class "Default")
      (node (ref "D5") (pin "4") (pinfunction "B_4") (pintype "passive"))
      (node (ref "R20") (pin "2") (pinfunction "2_2") (pintype "passive"))
    )
    (net (code "28") (name "Net-(D5-G)") (class "Default")
      (node (ref "D5") (pin "3") (pinfunction "G_3") (pintype "passive"))
      (node (ref "R17") (pin "2") (pinfunction "2_2") (pintype "passive"))
    )
    (net (code "29") (name "Net-(D5-R)") (class "Default")
      (node (ref "D5") (pin "2") (pinfunction "R_2") (pintype "passive"))
      (node (ref "R16") (pin "2") (pinfunction "2_2") (pintype "passive"))
    )
    (net (code "30") (name "Net-(J2-Pad8)") (class "Default")
      (node (ref "J2") (pin "8") (pinfunction "8_8") (pintype "passive"))
      (node (ref "R6") (pin "2") (pinfunction "2_2") (pintype "passive"))
    )
    (net (code "31") (name "Net-(J2-Pad11)") (class "Default")
      (node (ref "J2") (pin "11") (pinfunction "11_11") (pintype "passive"))
      (node (ref "R5") (pin "2") (pinfunction "2_2") (pintype "passive"))
    )
    (net (code "32") (name "Net-(J2-Pad12)") (class "Default")
      (node (ref "J2") (pin "12") (pinfunction "12_12") (pintype "passive"))
      (node (ref "R4") (pin "2") (pinfunction "2_2") (pintype "passive"))
    )
    (net (code "33") (name "Net-(TP1-TP)") (class "Default")
      (node (ref "C1") (pin "1") (pinfunction "1_1") (pintype "passive"))
      (node (ref "TP1") (pin "1") (pinfunction "TP_1") (pintype "passive"))
      (node (ref "U1") (pin "3") (pinfunction "S_3") (pintype "passive"))
      (node (ref "U2") (pin "1") (pinfunction "VCC_1") (pintype "passive"))
    )
    (net (code "34") (name "Net-(TP3-TP)") (class "Default")
      (node (ref "R1") (pin "2") (pinfunction "2_2") (pintype "passive"))
      (node (ref "TP3") (pin "1") (pinfunction "TP_1") (pintype "passive"))
      (node (ref "U1") (pin "1") (pinfunction "ON_1") (pintype "passive"))
    )
    (net (code "35") (name "Net-(TP27-TP)") (class "Default")
      (node (ref "R7") (pin "1") (pinfunction "1_1") (pintype "passive"))
      (node (ref "TP27") (pin "1") (pinfunction "TP_1") (pintype "passive"))
      (node (ref "U3") (pin "3") (pinfunction "S_3") (pintype "passive"))
    )
    (net (code "36") (name "Net-(TP31-TP)") (class "Default")
      (node (ref "R9") (pin "2") (pinfunction "2_2") (pintype "passive"))
      (node (ref "TP31") (pin "1") (pinfunction "TP_1") (pintype "passive"))
      (node (ref "U3") (pin "1") (pinfunction "ON_1") (pintype "passive"))
    )
    (net (code "37") (name "Net-(TP32-TP)") (class "Default")
      (node (ref "D1") (pin "A") (pinfunction "A_A") (pintype "passive"))
      (node (ref "J2") (pin "1") (pinfunction "1_1") (pintype "passive"))
      (node (ref "J2") (pin "2") (pinfunction "2_2") (pintype "passive"))
      (node (ref "Q1") (pin "D") (pinfunction "D_D") (pintype "passive"))
      (node (ref "TP32") (pin "1") (pinfunction "TP_1") (pintype "passive"))
    )
    (net (code "38") (name "Net-(TP33-TP)") (class "Default")
      (node (ref "Q1") (pin "G") (pinfunction "G_G") (pintype "passive"))
      (node (ref "R11") (pin "2") (pinfunction "2_2") (pintype "passive"))
      (node (ref "R12") (pin "1") (pinfunction "1_1") (pintype "passive"))
      (node (ref "TP33") (pin "1") (pinfunction "TP_1") (pintype "passive"))
    )
    (net (code "39") (name "VCC_3V3_APP") (class "Default")
      (node (ref "C3") (pin "2") (pinfunction "2_2") (pintype "passive"))
      (node (ref "C4") (pin "P") (pinfunction "POS_P") (pintype "passive"))
      (node (ref "C5") (pin "1") (pinfunction "1_1") (pintype "passive"))
      (node (ref "C8") (pin "2") (pinfunction "2_2") (pintype "passive"))
      (node (ref "D5") (pin "1") (pinfunction "ANODE_1") (pintype "passive"))
      (node (ref "J1") (pin "31") (pinfunction "31_31") (pintype "passive"))
      (node (ref "J1") (pin "33") (pinfunction "33_33") (pintype "passive"))
      (node (ref "J2") (pin "6") (pinfunction "6_6") (pintype "passive"))
      (node (ref "TP26") (pin "1") (pinfunction "TP_1") (pintype "passive"))
      (node (ref "U1") (pin "2") (pinfunction "D_2") (pintype "passive"))
      (node (ref "U3") (pin "2") (pinfunction "D_2") (pintype "passive"))
    )
    (net (code "40") (name "VCC_HAPTICS") (class "Default")
      (node (ref "C10") (pin "1") (pinfunction "1_1") (pintype "passive"))
      (node (ref "C9") (pin "1") (pinfunction "1_1") (pintype "passive"))
      (node (ref "D1") (pin "C") (pinfunction "C_C") (pintype "passive"))
      (node (ref "J2") (pin "3") (pinfunction "3_3") (pintype "passive"))
      (node (ref "J2") (pin "4") (pinfunction "4_4") (pintype "passive"))
      (node (ref "R8") (pin "2") (pinfunction "2_2") (pintype "passive"))
      (node (ref "TP29") (pin "1") (pinfunction "TP_1") (pintype "passive"))
    )
    (net (code "41") (name "unconnected-(J1-Pad27)") (class "Default")
      (node (ref "J1") (pin "27") (pinfunction "27_27") (pintype "passive+no_connect"))
    )
    (net (code "42") (name "unconnected-(J1-Pad28)") (class "Default")
      (node (ref "J1") (pin "28") (pinfunction "28_28") (pintype "passive+no_connect"))
    )
    (net (code "43") (name "unconnected-(J1-Pad30)") (class "Default")
      (node (ref "J1") (pin "30") (pinfunction "30_30") (pintype "passive+no_connect"))
    )
  )
)
